# Power.net
KiCad netlist of a schematic drawn in Altium Designer
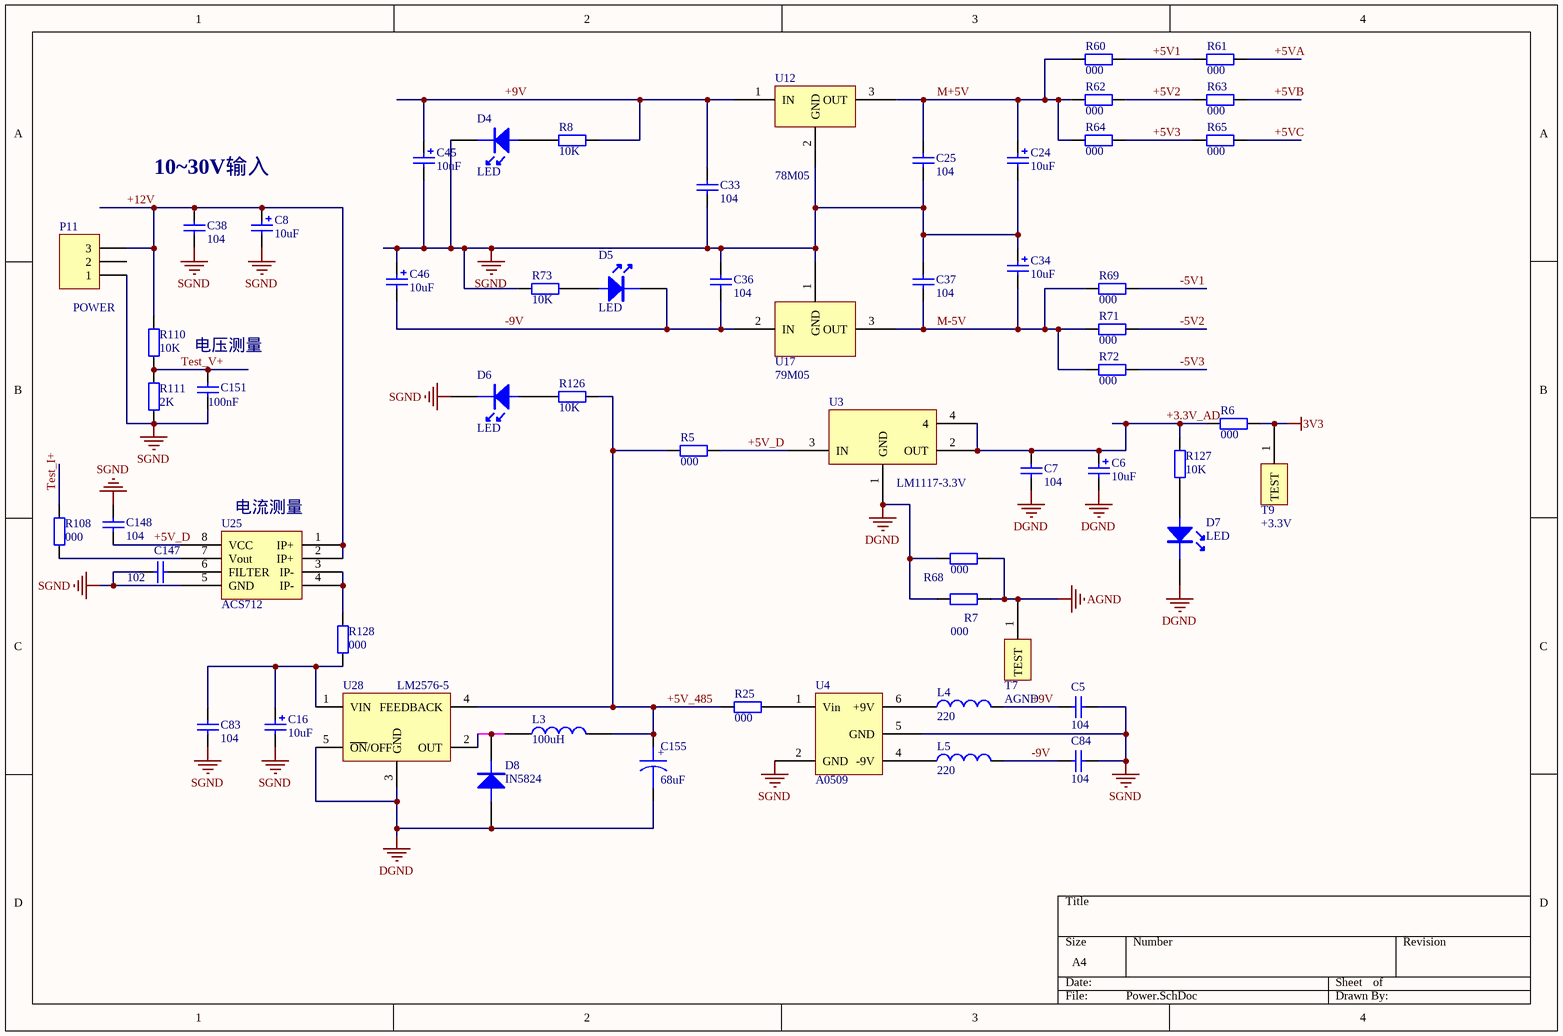
[diagram p0: Power.SchDoc]

(export (version "E")
  (design (tool "Eeschema 10.0.6"))
  (components
    (comp (ref "C5")
      (value "104")
      (footprint "0805C")
      (description "Capacitor")
      (fields (field (name "PUBLISHER") "Altium Limited"))
      (libsource (lib "Miscellaneous Devices") (part "Cap"))
    )
    (comp (ref "C6")
      (value "10uF")
      (footprint "C68uF")
      (description "Polarized Capacitor (Axial)")
      (fields (field (name "PUBLISHER") "Altium Limited"))
      (libsource (lib "Miscellaneous Devices") (part "Cap Pol2"))
    )
    (comp (ref "C7")
      (value "104")
      (footprint "0805C")
      (description "Capacitor")
      (fields (field (name "PUBLISHER") "Altium Limited"))
      (libsource (lib "Miscellaneous Devices") (part "Cap"))
    )
    (comp (ref "C8")
      (value "10uF")
      (footprint "C68uF")
      (description "Polarized Capacitor (Axial)")
      (fields (field (name "PUBLISHER") "Altium Limited"))
      (libsource (lib "Miscellaneous Devices") (part "Cap Pol2"))
    )
    (comp (ref "C16")
      (value "10uF")
      (footprint "C68uF")
      (description "Polarized Capacitor (Axial)")
      (fields (field (name "PUBLISHER") "Altium Limited"))
      (libsource (lib "Miscellaneous Devices") (part "Cap Pol2"))
    )
    (comp (ref "C24")
      (value "10uF")
      (footprint "C68uF")
      (description "Polarized Capacitor (Axial)")
      (fields (field (name "PUBLISHER") "Altium Limited"))
      (libsource (lib "Miscellaneous Devices") (part "Cap Pol2"))
    )
    (comp (ref "C25")
      (value "104")
      (footprint "0805C")
      (description "Capacitor")
      (fields (field (name "PUBLISHER") "Altium Limited"))
      (libsource (lib "Miscellaneous Devices") (part "Cap"))
    )
    (comp (ref "C33")
      (value "104")
      (footprint "0805C")
      (description "Capacitor")
      (fields (field (name "PUBLISHER") "Altium Limited"))
      (libsource (lib "Miscellaneous Devices") (part "Cap"))
    )
    (comp (ref "C34")
      (value "10uF")
      (footprint "C68uF")
      (description "Polarized Capacitor (Axial)")
      (fields (field (name "PUBLISHER") "Altium Limited"))
      (libsource (lib "Miscellaneous Devices") (part "Cap Pol2"))
    )
    (comp (ref "C36")
      (value "104")
      (footprint "0805C")
      (description "Capacitor")
      (fields (field (name "PUBLISHER") "Altium Limited"))
      (libsource (lib "Miscellaneous Devices") (part "Cap"))
    )
    (comp (ref "C37")
      (value "104")
      (footprint "0805C")
      (description "Capacitor")
      (fields (field (name "PUBLISHER") "Altium Limited"))
      (libsource (lib "Miscellaneous Devices") (part "Cap"))
    )
    (comp (ref "C38")
      (value "104")
      (footprint "0805C")
      (description "Capacitor")
      (fields (field (name "PUBLISHER") "Altium Limited"))
      (libsource (lib "Miscellaneous Devices") (part "Cap"))
    )
    (comp (ref "C45")
      (value "10uF")
      (footprint "C68uF")
      (description "Polarized Capacitor (Axial)")
      (fields (field (name "PUBLISHER") "Altium Limited"))
      (libsource (lib "Miscellaneous Devices") (part "Cap Pol2"))
    )
    (comp (ref "C46")
      (value "10uF")
      (footprint "C68uF")
      (description "Polarized Capacitor (Axial)")
      (fields (field (name "PUBLISHER") "Altium Limited"))
      (libsource (lib "Miscellaneous Devices") (part "Cap Pol2"))
    )
    (comp (ref "C83")
      (value "104")
      (footprint "0805C")
      (description "Capacitor")
      (fields (field (name "PUBLISHER") "Altium Limited"))
      (libsource (lib "Miscellaneous Devices") (part "Cap"))
    )
    (comp (ref "C84")
      (value "104")
      (footprint "0805C")
      (description "Capacitor")
      (fields (field (name "PUBLISHER") "Altium Limited"))
      (libsource (lib "Miscellaneous Devices") (part "Cap"))
    )
    (comp (ref "C147")
      (value "102")
      (footprint "0603")
      (description "Capacitor")
      (fields (field (name "PUBLISHER") "Altium Limited"))
      (libsource (lib "Miscellaneous Devices") (part "Cap"))
    )
    (comp (ref "C148")
      (value "104")
      (footprint "0603")
      (description "Capacitor")
      (fields (field (name "PUBLISHER") "Altium Limited"))
      (libsource (lib "Miscellaneous Devices") (part "Cap"))
    )
    (comp (ref "C151")
      (value "100nF")
      (footprint "0603")
      (description "Capacitor")
      (fields (field (name "Comment") "Cap") (field (name "PUBLISHER") "Altium Limited"))
      (libsource (lib "Miscellaneous Devices") (part "Cap"))
    )
    (comp (ref "C155")
      (value "68uF")
      (footprint "C68uF")
      (description "Capacitor")
      (libsource (lib "*") (part "CAPACITOR POL"))
    )
    (comp (ref "D4") (value "LED") (footprint "0805_LED") (libsource (lib "*") (part "LED")))
    (comp (ref "D5") (value "LED") (footprint "0805_LED") (libsource (lib "*") (part "LED")))
    (comp (ref "D6") (value "LED") (footprint "0805_LED") (libsource (lib "*") (part "LED")))
    (comp (ref "D7") (value "LED") (footprint "0805_LED") (libsource (lib "*") (part "LED")))
    (comp (ref "D8")
      (value "IN5824")
      (footprint "1N5824")
      (description "Diode")
      (libsource (lib "*") (part "DIODE"))
    )
    (comp (ref "L3") (value "100uH") (footprint "L100uH") (libsource (lib "*") (part "INDUCTOR")))
    (comp (ref "L4")
      (value "220")
      (footprint "1206")
      (description "Inductor")
      (fields (field (name "PUBLISHER") "Altium Limited"))
      (libsource (lib "Miscellaneous Devices") (part "Inductor"))
    )
    (comp (ref "L5")
      (value "220")
      (footprint "1206")
      (description "Inductor")
      (fields (field (name "PUBLISHER") "Altium Limited"))
      (libsource (lib "Miscellaneous Devices") (part "Inductor"))
    )
    (comp (ref "P11")
      (value "POWER")
      (footprint "SIP3-5.08mm")
      (description "Header, 3-Pin")
      (fields (field (name "PUBLISHER") "Altium Limited"))
      (libsource (lib "Miscellaneous Connectors") (part "Header 3"))
    )
    (comp (ref "R5")
      (value "000")
      (footprint "0805R")
      (description "Resistor")
      (fields (field (name "PUBLISHER") "Altium Limited"))
      (libsource (lib "Miscellaneous Devices") (part "Res2"))
    )
    (comp (ref "R6")
      (value "000")
      (footprint "0805R")
      (description "Resistor")
      (fields (field (name "PUBLISHER") "Altium Limited"))
      (libsource (lib "Miscellaneous Devices") (part "Res2"))
    )
    (comp (ref "R7")
      (value "000")
      (footprint "I_ON")
      (description "Resistor")
      (fields (field (name "PUBLISHER") "Altium Limited"))
      (libsource (lib "Miscellaneous Devices") (part "Res2"))
    )
    (comp (ref "R8")
      (value "10K")
      (footprint "0603")
      (description "Resistor")
      (fields (field (name "Comment") "Res2") (field (name "PUBLISHER") "Altium Limited"))
      (libsource (lib "") (part "Res2_2"))
    )
    (comp (ref "R25")
      (value "000")
      (footprint "0805R")
      (description "Resistor")
      (fields (field (name "PUBLISHER") "Altium Limited"))
      (libsource (lib "Miscellaneous Devices") (part "Res2"))
    )
    (comp (ref "R60")
      (value "000")
      (footprint "0805R")
      (description "Resistor")
      (fields (field (name "PUBLISHER") "Altium Limited"))
      (libsource (lib "Miscellaneous Devices") (part "Res2"))
    )
    (comp (ref "R61")
      (value "000")
      (footprint "0805R")
      (description "Resistor")
      (fields (field (name "PUBLISHER") "Altium Limited"))
      (libsource (lib "Miscellaneous Devices") (part "Res2"))
    )
    (comp (ref "R62")
      (value "000")
      (footprint "0805R")
      (description "Resistor")
      (fields (field (name "PUBLISHER") "Altium Limited"))
      (libsource (lib "Miscellaneous Devices") (part "Res2"))
    )
    (comp (ref "R63")
      (value "000")
      (footprint "0805R")
      (description "Resistor")
      (fields (field (name "PUBLISHER") "Altium Limited"))
      (libsource (lib "Miscellaneous Devices") (part "Res2"))
    )
    (comp (ref "R64")
      (value "000")
      (footprint "0805R")
      (description "Resistor")
      (fields (field (name "PUBLISHER") "Altium Limited"))
      (libsource (lib "Miscellaneous Devices") (part "Res2"))
    )
    (comp (ref "R65")
      (value "000")
      (footprint "0805R")
      (description "Resistor")
      (fields (field (name "PUBLISHER") "Altium Limited"))
      (libsource (lib "Miscellaneous Devices") (part "Res2"))
    )
    (comp (ref "R68")
      (value "000")
      (footprint "I_ON")
      (description "Resistor")
      (fields (field (name "PUBLISHER") "Altium Limited"))
      (libsource (lib "Miscellaneous Devices") (part "Res2"))
    )
    (comp (ref "R69")
      (value "000")
      (footprint "0805R")
      (description "Resistor")
      (fields (field (name "PUBLISHER") "Altium Limited"))
      (libsource (lib "Miscellaneous Devices") (part "Res2"))
    )
    (comp (ref "R71")
      (value "000")
      (footprint "0805R")
      (description "Resistor")
      (fields (field (name "PUBLISHER") "Altium Limited"))
      (libsource (lib "Miscellaneous Devices") (part "Res2"))
    )
    (comp (ref "R72")
      (value "000")
      (footprint "0805R")
      (description "Resistor")
      (fields (field (name "PUBLISHER") "Altium Limited"))
      (libsource (lib "Miscellaneous Devices") (part "Res2"))
    )
    (comp (ref "R73")
      (value "10K")
      (footprint "0603")
      (description "Resistor")
      (fields (field (name "Comment") "Res2") (field (name "PUBLISHER") "Altium Limited"))
      (libsource (lib "Miscellaneous Devices") (part "Res2"))
    )
    (comp (ref "R108")
      (value "000")
      (footprint "0603")
      (description "Resistor")
      (fields (field (name "PUBLISHER") "Altium Limited"))
      (libsource (lib "") (part "Res2_1"))
    )
    (comp (ref "R110")
      (value "10K")
      (footprint "0603")
      (description "Resistor")
      (fields (field (name "Comment") "Res2") (field (name "PUBLISHER") "Altium Limited"))
      (libsource (lib "") (part "Res2_3"))
    )
    (comp (ref "R111")
      (value "2K")
      (footprint "0603")
      (description "Resistor")
      (fields (field (name "Comment") "Res2") (field (name "PUBLISHER") "Altium Limited"))
      (libsource (lib "") (part "Res2_1"))
    )
    (comp (ref "R126")
      (value "10K")
      (footprint "0603")
      (description "Resistor")
      (fields (field (name "Comment") "Res2") (field (name "PUBLISHER") "Altium Limited"))
      (libsource (lib "") (part "Res2_2"))
    )
    (comp (ref "R127")
      (value "10K")
      (footprint "0603")
      (description "Resistor")
      (fields (field (name "Comment") "Res2") (field (name "PUBLISHER") "Altium Limited"))
      (libsource (lib "") (part "Res2_3"))
    )
    (comp (ref "R128")
      (value "000")
      (footprint "0805R")
      (description "Resistor")
      (fields (field (name "PUBLISHER") "Altium Limited"))
      (libsource (lib "") (part "Res2_1"))
    )
    (comp (ref "T7") (value "AGND") (footprint "TEST") (libsource (lib "Schlib1") (part "TEST")))
    (comp (ref "T9") (value "+3.3V") (footprint "TEST") (libsource (lib "Schlib1") (part "TEST")))
    (comp (ref "U3")
      (value "LM1117-3.3V")
      (footprint "SOT223")
      (libsource (lib "Schlib1") (part "LM1117-3.3V"))
    )
    (comp (ref "U4") (value "A0509") (footprint "A0509S") (libsource (lib "Schlib1") (part "A0509")))
    (comp (ref "U12") (value "78M05") (footprint "7XM05") (libsource (lib "Schlib1") (part "78M05G")))
    (comp (ref "U17") (value "79M05") (footprint "7XM05") (libsource (lib "Schlib1") (part "79L05")))
    (comp (ref "U25") (value "ACS712") (footprint "SO8") (libsource (lib "Schlib1") (part "ACS712")))
    (comp (ref "U28") (value "LM2576-5") (footprint "lm2596") (libsource (lib "*") (part "LM2596-5")))
  )
  (nets
    (net (code "1") (name "/+3.3V_AD") (class "Default")
      (node (ref "C6") (pin "1") (pinfunction "1_1") (pintype "passive"))
      (node (ref "C7") (pin "1") (pinfunction "1_1") (pintype "passive"))
      (node (ref "R127") (pin "2") (pinfunction "2_2") (pintype "passive"))
      (node (ref "R6") (pin "2") (pinfunction "2_2") (pintype "passive"))
      (node (ref "U3") (pin "2") (pinfunction "OUT_2") (pintype "passive"))
      (node (ref "U3") (pin "4") (pinfunction "4_4") (pintype "passive"))
    )
    (net (code "2") (name "/+5V1") (class "Default")
      (node (ref "R60") (pin "1") (pinfunction "1_1") (pintype "passive"))
      (node (ref "R61") (pin "2") (pinfunction "2_2") (pintype "passive"))
    )
    (net (code "3") (name "/+5V2") (class "Default")
      (node (ref "R62") (pin "1") (pinfunction "1_1") (pintype "passive"))
      (node (ref "R63") (pin "2") (pinfunction "2_2") (pintype "passive"))
    )
    (net (code "4") (name "/+5V3") (class "Default")
      (node (ref "R64") (pin "1") (pinfunction "1_1") (pintype "passive"))
      (node (ref "R65") (pin "2") (pinfunction "2_2") (pintype "passive"))
    )
    (net (code "5") (name "/+5VA") (class "Default")
      (node (ref "R61") (pin "1") (pinfunction "1_1") (pintype "passive"))
    )
    (net (code "6") (name "/+5VB") (class "Default")
      (node (ref "R63") (pin "1") (pinfunction "1_1") (pintype "passive"))
    )
    (net (code "7") (name "/+5VC") (class "Default")
      (node (ref "R65") (pin "1") (pinfunction "1_1") (pintype "passive"))
    )
    (net (code "8") (name "/+5V_485") (class "Default")
      (node (ref "C155") (pin "1") (pinfunction "1_1") (pintype "passive"))
      (node (ref "L3") (pin "2") (pinfunction "2_2") (pintype "passive"))
      (node (ref "R126") (pin "2") (pinfunction "2_2") (pintype "passive"))
      (node (ref "R25") (pin "2") (pinfunction "2_2") (pintype "passive"))
      (node (ref "R5") (pin "2") (pinfunction "2_2") (pintype "passive"))
      (node (ref "U28") (pin "4") (pinfunction "FEEDBACK_4") (pintype "passive"))
    )
    (net (code "9") (name "/+5V_D") (class "Default")
      (node (ref "C148") (pin "2") (pinfunction "2_2") (pintype "passive"))
      (node (ref "R5") (pin "1") (pinfunction "1_1") (pintype "passive"))
      (node (ref "U25") (pin "8") (pinfunction "VCC_8") (pintype "passive"))
      (node (ref "U3") (pin "3") (pinfunction "IN_3") (pintype "passive"))
    )
    (net (code "10") (name "/+9V") (class "Default")
      (node (ref "C33") (pin "1") (pinfunction "1_1") (pintype "passive"))
      (node (ref "C45") (pin "1") (pinfunction "1_1") (pintype "passive"))
      (node (ref "C5") (pin "1") (pinfunction "1_1") (pintype "passive"))
      (node (ref "L4") (pin "2") (pinfunction "2_2") (pintype "passive"))
      (node (ref "R8") (pin "2") (pinfunction "2_2") (pintype "passive"))
      (node (ref "U12") (pin "1") (pinfunction "IN_1") (pintype "passive"))
    )
    (net (code "11") (name "/+12V") (class "Default")
      (node (ref "C38") (pin "1") (pinfunction "1_1") (pintype "passive"))
      (node (ref "C8") (pin "1") (pinfunction "1_1") (pintype "passive"))
      (node (ref "P11") (pin "3") (pinfunction "3_3") (pintype "passive"))
      (node (ref "R110") (pin "2") (pinfunction "2_2") (pintype "passive"))
      (node (ref "U25") (pin "1") (pinfunction "IP+_1") (pintype "passive"))
      (node (ref "U25") (pin "2") (pinfunction "IP+_2") (pintype "passive"))
    )
    (net (code "12") (name "/-5V1") (class "Default")
      (node (ref "R69") (pin "1") (pinfunction "1_1") (pintype "passive"))
    )
    (net (code "13") (name "/-5V2") (class "Default")
      (node (ref "R71") (pin "1") (pinfunction "1_1") (pintype "passive"))
    )
    (net (code "14") (name "/-5V3") (class "Default")
      (node (ref "R72") (pin "1") (pinfunction "1_1") (pintype "passive"))
    )
    (net (code "15") (name "/-9V") (class "Default")
      (node (ref "C36") (pin "2") (pinfunction "2_2") (pintype "passive"))
      (node (ref "C46") (pin "2") (pinfunction "2_2") (pintype "passive"))
      (node (ref "C84") (pin "1") (pinfunction "1_1") (pintype "passive"))
      (node (ref "D5") (pin "2") (pinfunction "K_2") (pintype "passive"))
      (node (ref "L5") (pin "2") (pinfunction "2_2") (pintype "passive"))
      (node (ref "U17") (pin "2") (pinfunction "IN_2") (pintype "passive"))
    )
    (net (code "16") (name "/M+5V") (class "Default")
      (node (ref "C24") (pin "1") (pinfunction "1_1") (pintype "passive"))
      (node (ref "C25") (pin "1") (pinfunction "1_1") (pintype "passive"))
      (node (ref "R60") (pin "2") (pinfunction "2_2") (pintype "passive"))
      (node (ref "R62") (pin "2") (pinfunction "2_2") (pintype "passive"))
      (node (ref "R64") (pin "2") (pinfunction "2_2") (pintype "passive"))
      (node (ref "U12") (pin "3") (pinfunction "OUT_3") (pintype "passive"))
    )
    (net (code "17") (name "/M-5V") (class "Default")
      (node (ref "C34") (pin "2") (pinfunction "2_2") (pintype "passive"))
      (node (ref "C37") (pin "2") (pinfunction "2_2") (pintype "passive"))
      (node (ref "R69") (pin "2") (pinfunction "2_2") (pintype "passive"))
      (node (ref "R71") (pin "2") (pinfunction "2_2") (pintype "passive"))
      (node (ref "R72") (pin "2") (pinfunction "2_2") (pintype "passive"))
      (node (ref "U17") (pin "3") (pinfunction "OUT_3") (pintype "passive"))
    )
    (net (code "18") (name "/Test_I+") (class "Default")
      (node (ref "R108") (pin "1") (pinfunction "1_1") (pintype "passive"))
    )
    (net (code "19") (name "/Test_V+") (class "Default")
      (node (ref "C151") (pin "2") (pinfunction "2_2") (pintype "passive"))
      (node (ref "R110") (pin "1") (pinfunction "1_1") (pintype "passive"))
      (node (ref "R111") (pin "1") (pinfunction "1_1") (pintype "passive"))
    )
    (net (code "20") (name "3V3") (class "Default")
      (node (ref "R6") (pin "1") (pinfunction "1_1") (pintype "passive"))
      (node (ref "T9") (pin "1") (pinfunction "TEST_1") (pintype "passive"))
    )
    (net (code "21") (name "AGND") (class "Default")
      (node (ref "R68") (pin "1") (pinfunction "1_1") (pintype "passive"))
      (node (ref "R7") (pin "1") (pinfunction "1_1") (pintype "passive"))
      (node (ref "T7") (pin "1") (pinfunction "TEST_1") (pintype "passive"))
    )
    (net (code "22") (name "DGND") (class "Default")
      (node (ref "C155") (pin "2") (pinfunction "2_2") (pintype "passive"))
      (node (ref "C6") (pin "2") (pinfunction "2_2") (pintype "passive"))
      (node (ref "C7") (pin "2") (pinfunction "2_2") (pintype "passive"))
      (node (ref "D7") (pin "2") (pinfunction "K_2") (pintype "passive"))
      (node (ref "D8") (pin "1") (pinfunction "A_1") (pintype "passive"))
      (node (ref "R68") (pin "2") (pinfunction "2_2") (pintype "passive"))
      (node (ref "R7") (pin "2") (pinfunction "2_2") (pintype "passive"))
      (node (ref "U28") (pin "3") (pinfunction "GND_3") (pintype "passive"))
      (node (ref "U28") (pin "5") (pinfunction "~{ON}/OFF_5") (pintype "passive"))
      (node (ref "U3") (pin "1") (pinfunction "GND_1") (pintype "passive"))
    )
    (net (code "23") (name "Net-(D4-A)") (class "Default")
      (node (ref "D4") (pin "1") (pinfunction "A_1") (pintype "passive"))
      (node (ref "R8") (pin "1") (pinfunction "1_1") (pintype "passive"))
    )
    (net (code "24") (name "Net-(D5-A)") (class "Default")
      (node (ref "D5") (pin "1") (pinfunction "A_1") (pintype "passive"))
      (node (ref "R73") (pin "1") (pinfunction "1_1") (pintype "passive"))
    )
    (net (code "25") (name "Net-(D6-A)") (class "Default")
      (node (ref "D6") (pin "1") (pinfunction "A_1") (pintype "passive"))
      (node (ref "R126") (pin "1") (pinfunction "1_1") (pintype "passive"))
    )
    (net (code "26") (name "Net-(D7-A)") (class "Default")
      (node (ref "D7") (pin "1") (pinfunction "A_1") (pintype "passive"))
      (node (ref "R127") (pin "1") (pinfunction "1_1") (pintype "passive"))
    )
    (net (code "27") (name "Net-(D8-K)") (class "Default")
      (node (ref "D8") (pin "2") (pinfunction "K_2") (pintype "passive"))
      (node (ref "L3") (pin "1") (pinfunction "1_1") (pintype "passive"))
      (node (ref "U28") (pin "2") (pinfunction "OUT_2") (pintype "passive"))
    )
    (net (code "28") (name "Net-(R128-Pad1)") (class "Default")
      (node (ref "R128") (pin "1") (pinfunction "1_1") (pintype "passive"))
      (node (ref "U25") (pin "3") (pinfunction "IP-_3") (pintype "passive"))
      (node (ref "U25") (pin "4") (pinfunction "IP-_4") (pintype "passive"))
    )
    (net (code "29") (name "Net-(U4-+9V)") (class "Default")
      (node (ref "L4") (pin "1") (pinfunction "1_1") (pintype "passive"))
      (node (ref "U4") (pin "6") (pinfunction "+9V_6") (pintype "passive"))
    )
    (net (code "30") (name "Net-(U4--9V)") (class "Default")
      (node (ref "L5") (pin "1") (pinfunction "1_1") (pintype "passive"))
      (node (ref "U4") (pin "4") (pinfunction "-9V_4") (pintype "passive"))
    )
    (net (code "31") (name "Net-(U4-Vin)") (class "Default")
      (node (ref "R25") (pin "1") (pinfunction "1_1") (pintype "passive"))
      (node (ref "U4") (pin "1") (pinfunction "Vin_1") (pintype "passive"))
    )
    (net (code "32") (name "Net-(U25-FILTER)") (class "Default")
      (node (ref "C147") (pin "2") (pinfunction "2_2") (pintype "passive"))
      (node (ref "U25") (pin "6") (pinfunction "FILTER_6") (pintype "passive"))
    )
    (net (code "33") (name "Net-(U25-Vout)") (class "Default")
      (node (ref "R108") (pin "2") (pinfunction "2_2") (pintype "passive"))
      (node (ref "U25") (pin "7") (pinfunction "Vout_7") (pintype "passive"))
    )
    (net (code "34") (name "Net-(U28-VIN)") (class "Default")
      (node (ref "C16") (pin "1") (pinfunction "1_1") (pintype "passive"))
      (node (ref "C83") (pin "1") (pinfunction "1_1") (pintype "passive"))
      (node (ref "R128") (pin "2") (pinfunction "2_2") (pintype "passive"))
      (node (ref "U28") (pin "1") (pinfunction "VIN_1") (pintype "passive"))
    )
    (net (code "35") (name "SGND") (class "Default")
      (node (ref "C147") (pin "1") (pinfunction "1_1") (pintype "passive"))
      (node (ref "C148") (pin "1") (pinfunction "1_1") (pintype "passive"))
      (node (ref "C151") (pin "1") (pinfunction "1_1") (pintype "passive"))
      (node (ref "C16") (pin "2") (pinfunction "2_2") (pintype "passive"))
      (node (ref "C24") (pin "2") (pinfunction "2_2") (pintype "passive"))
      (node (ref "C25") (pin "2") (pinfunction "2_2") (pintype "passive"))
      (node (ref "C33") (pin "2") (pinfunction "2_2") (pintype "passive"))
      (node (ref "C34") (pin "1") (pinfunction "1_1") (pintype "passive"))
      (node (ref "C36") (pin "1") (pinfunction "1_1") (pintype "passive"))
      (node (ref "C37") (pin "1") (pinfunction "1_1") (pintype "passive"))
      (node (ref "C38") (pin "2") (pinfunction "2_2") (pintype "passive"))
      (node (ref "C45") (pin "2") (pinfunction "2_2") (pintype "passive"))
      (node (ref "C46") (pin "1") (pinfunction "1_1") (pintype "passive"))
      (node (ref "C5") (pin "2") (pinfunction "2_2") (pintype "passive"))
      (node (ref "C8") (pin "2") (pinfunction "2_2") (pintype "passive"))
      (node (ref "C83") (pin "2") (pinfunction "2_2") (pintype "passive"))
      (node (ref "C84") (pin "2") (pinfunction "2_2") (pintype "passive"))
      (node (ref "D4") (pin "2") (pinfunction "K_2") (pintype "passive"))
      (node (ref "D6") (pin "2") (pinfunction "K_2") (pintype "passive"))
      (node (ref "P11") (pin "1") (pinfunction "1_1") (pintype "passive"))
      (node (ref "R111") (pin "2") (pinfunction "2_2") (pintype "passive"))
      (node (ref "R73") (pin "2") (pinfunction "2_2") (pintype "passive"))
      (node (ref "U12") (pin "2") (pinfunction "GND_2") (pintype "passive"))
      (node (ref "U17") (pin "1") (pinfunction "GND_1") (pintype "passive"))
      (node (ref "U25") (pin "5") (pinfunction "GND_5") (pintype "passive"))
      (node (ref "U4") (pin "2") (pinfunction "GND_2") (pintype "passive"))
      (node (ref "U4") (pin "5") (pinfunction "GND_5") (pintype "passive"))
    )
    (net (code "36") (name "unconnected-(P11-Pad2)") (class "Default")
      (node (ref "P11") (pin "2") (pinfunction "2_2") (pintype "passive"))
    )
  )
)
